# mpu6500.net
KiCad netlist of a schematic drawn in Altium Designer
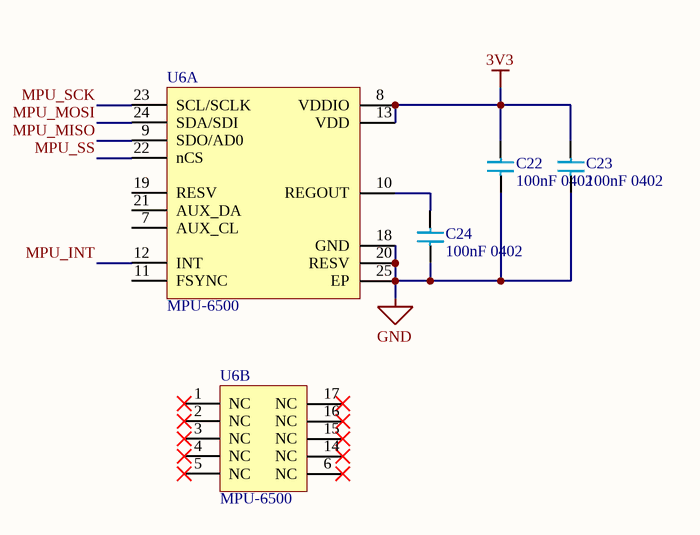
[diagram p0: mpu6500.SchDoc]

(export (version "E")
  (design (tool "Eeschema 10.0.6"))
  (components
    (comp (ref "C22")
      (value "100nF 0402")
      (footprint "C0402")
      (libsource (lib "robot-cortex") (part "C0402-100nF"))
    )
    (comp (ref "C23")
      (value "100nF 0402")
      (footprint "C0402")
      (libsource (lib "robot-cortex") (part "C0402-100nF"))
    )
    (comp (ref "C24")
      (value "100nF 0402")
      (footprint "C0402")
      (libsource (lib "robot-cortex") (part "C0402-100nF"))
    )
    (comp (ref "U6")
      (value "MPU-6500")
      (footprint "QFN24")
      (description "GYRO/ACCELEROMETER 6AXIS 24QFN")
      (fields (field (name "MANUFACTURER") "TDK InvenSense"))
      (libsource (lib "robot-cortex") (part "MPU-6500"))
    )
  )
  (nets
    (net (code "1") (name "/MPU_INT") (class "Default")
      (node (ref "U6") (pin "12") (pinfunction "INT_12") (pintype "passive"))
    )
    (net (code "2") (name "/MPU_MISO") (class "Default")
      (node (ref "U6") (pin "9") (pinfunction "SDO/AD0_9") (pintype "passive"))
    )
    (net (code "3") (name "/MPU_MOSI") (class "Default")
      (node (ref "U6") (pin "24") (pinfunction "SDA/SDI_24") (pintype "passive"))
    )
    (net (code "4") (name "/MPU_SCK") (class "Default")
      (node (ref "U6") (pin "23") (pinfunction "SCL/SCLK_23") (pintype "passive"))
    )
    (net (code "5") (name "/MPU_SS") (class "Default")
      (node (ref "U6") (pin "22") (pinfunction "nCS_22") (pintype "passive"))
    )
    (net (code "6") (name "3V3") (class "Default")
      (node (ref "C22") (pin "1") (pinfunction "1_1") (pintype "passive"))
      (node (ref "C23") (pin "1") (pinfunction "1_1") (pintype "passive"))
      (node (ref "U6") (pin "13") (pinfunction "VDD_13") (pintype "passive"))
      (node (ref "U6") (pin "8") (pinfunction "VDDIO_8") (pintype "passive"))
    )
    (net (code "7") (name "GND") (class "Default")
      (node (ref "C22") (pin "2") (pinfunction "2_2") (pintype "passive"))
      (node (ref "C23") (pin "2") (pinfunction "2_2") (pintype "passive"))
      (node (ref "C24") (pin "2") (pinfunction "2_2") (pintype "passive"))
      (node (ref "U6") (pin "18") (pinfunction "GND_18") (pintype "passive"))
      (node (ref "U6") (pin "20") (pinfunction "RESV_20") (pintype "passive"))
      (node (ref "U6") (pin "25") (pinfunction "EP_25") (pintype "passive"))
    )
    (net (code "8") (name "Net-(U6A-REGOUT)") (class "Default")
      (node (ref "C24") (pin "1") (pinfunction "1_1") (pintype "passive"))
      (node (ref "U6") (pin "10") (pinfunction "REGOUT_10") (pintype "passive"))
    )
    (net (code "9") (name "unconnected-(U6A-AUX_CL-Pad7)") (class "Default")
      (node (ref "U6") (pin "7") (pinfunction "AUX_CL_7") (pintype "passive"))
    )
    (net (code "10") (name "unconnected-(U6A-AUX_DA-Pad21)") (class "Default")
      (node (ref "U6") (pin "21") (pinfunction "AUX_DA_21") (pintype "passive"))
    )
    (net (code "11") (name "unconnected-(U6A-FSYNC-Pad11)") (class "Default")
      (node (ref "U6") (pin "11") (pinfunction "FSYNC_11") (pintype "passive"))
    )
    (net (code "12") (name "unconnected-(U6A-RESV-Pad19)") (class "Default")
      (node (ref "U6") (pin "19") (pinfunction "RESV_19") (pintype "passive"))
    )
    (net (code "13") (name "unconnected-(U6B-NC-Pad1)") (class "Default")
      (node (ref "U6") (pin "1") (pinfunction "NC_1") (pintype "passive+no_connect"))
    )
    (net (code "14") (name "unconnected-(U6B-NC-Pad2)") (class "Default")
      (node (ref "U6") (pin "2") (pinfunction "NC_2") (pintype "passive+no_connect"))
    )
    (net (code "15") (name "unconnected-(U6B-NC-Pad3)") (class "Default")
      (node (ref "U6") (pin "3") (pinfunction "NC_3") (pintype "passive+no_connect"))
    )
    (net (code "16") (name "unconnected-(U6B-NC-Pad4)") (class "Default")
      (node (ref "U6") (pin "4") (pinfunction "NC_4") (pintype "passive+no_connect"))
    )
    (net (code "17") (name "unconnected-(U6B-NC-Pad5)") (class "Default")
      (node (ref "U6") (pin "5") (pinfunction "NC_5") (pintype "passive+no_connect"))
    )
    (net (code "18") (name "unconnected-(U6B-NC-Pad6)") (class "Default")
      (node (ref "U6") (pin "6") (pinfunction "NC_6") (pintype "passive+no_connect"))
    )
    (net (code "19") (name "unconnected-(U6B-NC-Pad14)") (class "Default")
      (node (ref "U6") (pin "14") (pinfunction "NC_14") (pintype "passive+no_connect"))
    )
    (net (code "20") (name "unconnected-(U6B-NC-Pad15)") (class "Default")
      (node (ref "U6") (pin "15") (pinfunction "NC_15") (pintype "passive+no_connect"))
    )
    (net (code "21") (name "unconnected-(U6B-NC-Pad16)") (class "Default")
      (node (ref "U6") (pin "16") (pinfunction "NC_16") (pintype "passive+no_connect"))
    )
    (net (code "22") (name "unconnected-(U6B-NC-Pad17)") (class "Default")
      (node (ref "U6") (pin "17") (pinfunction "NC_17") (pintype "passive+no_connect"))
    )
  )
)
